# 128x64.net
KiCad netlist of a schematic drawn in Altium Designer
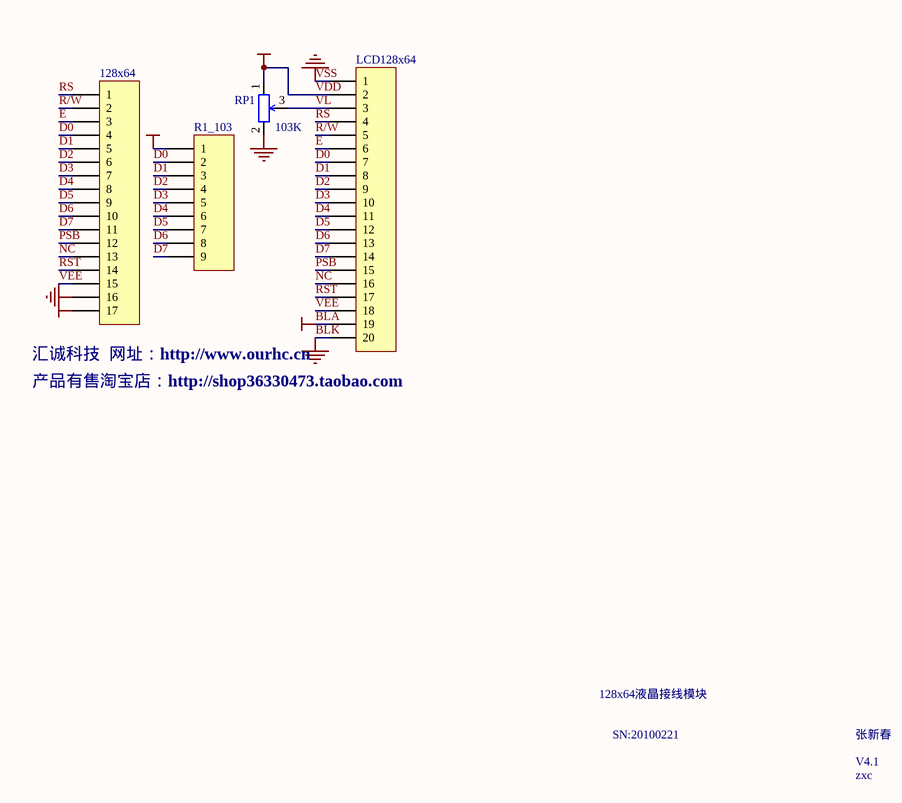
[diagram p0: 128x64液晶接线模块.SCHDOC]

(export (version "E")
  (design (tool "Eeschema 10.0.6"))
  (components
    (comp (ref "128x64")
      (value "Header 17")
      (footprint "HDR1X17")
      (description "Header, 17-Pin")
      (fields (field (name "PUBLISHER") "Altium Limited"))
      (libsource (lib "Miscellaneous Connectors") (part "Header 17"))
    )
    (comp (ref "LCD128x64")
      (value "Header 20")
      (footprint "HDR1X20")
      (description "Header, 20-Pin")
      (fields (field (name "PUBLISHER") "Altium Limited"))
      (libsource (lib "Miscellaneous Connectors") (part "Header 20"))
    )
    (comp (ref "R1_103")
      (value "Header 9")
      (footprint "HDR1X9")
      (description "Header, 9-Pin")
      (fields (field (name "PUBLISHER") "Altium Limited"))
      (libsource (lib "Miscellaneous Connectors") (part "Header 9"))
    )
    (comp (ref "RP1")
      (value "103K")
      (footprint "SIP3-D")
      (description "j精调电阻")
      (fields (field (name "Comment") "Res _JT") (field (name "PUBLISHER") "Altium Limited"))
      (libsource (lib "zxcourhc") (part "Res _JT"))
    )
  )
  (nets
    (net (code "1") (name "/D0") (class "Default")
      (node (ref "128x64") (pin "4") (pinfunction "4_4") (pintype "passive"))
      (node (ref "LCD128x64") (pin "7") (pinfunction "7_7") (pintype "passive"))
      (node (ref "R1_103") (pin "2") (pinfunction "2_2") (pintype "passive"))
    )
    (net (code "2") (name "/D1") (class "Default")
      (node (ref "128x64") (pin "5") (pinfunction "5_5") (pintype "passive"))
      (node (ref "LCD128x64") (pin "8") (pinfunction "8_8") (pintype "passive"))
      (node (ref "R1_103") (pin "3") (pinfunction "3_3") (pintype "passive"))
    )
    (net (code "3") (name "/D2") (class "Default")
      (node (ref "128x64") (pin "6") (pinfunction "6_6") (pintype "passive"))
      (node (ref "LCD128x64") (pin "9") (pinfunction "9_9") (pintype "passive"))
      (node (ref "R1_103") (pin "4") (pinfunction "4_4") (pintype "passive"))
    )
    (net (code "4") (name "/D3") (class "Default")
      (node (ref "128x64") (pin "7") (pinfunction "7_7") (pintype "passive"))
      (node (ref "LCD128x64") (pin "10") (pinfunction "10_10") (pintype "passive"))
      (node (ref "R1_103") (pin "5") (pinfunction "5_5") (pintype "passive"))
    )
    (net (code "5") (name "/D4") (class "Default")
      (node (ref "128x64") (pin "8") (pinfunction "8_8") (pintype "passive"))
      (node (ref "LCD128x64") (pin "11") (pinfunction "11_11") (pintype "passive"))
      (node (ref "R1_103") (pin "6") (pinfunction "6_6") (pintype "passive"))
    )
    (net (code "6") (name "/D5") (class "Default")
      (node (ref "128x64") (pin "9") (pinfunction "9_9") (pintype "passive"))
      (node (ref "LCD128x64") (pin "12") (pinfunction "12_12") (pintype "passive"))
      (node (ref "R1_103") (pin "7") (pinfunction "7_7") (pintype "passive"))
    )
    (net (code "7") (name "/D6") (class "Default")
      (node (ref "128x64") (pin "10") (pinfunction "10_10") (pintype "passive"))
      (node (ref "LCD128x64") (pin "13") (pinfunction "13_13") (pintype "passive"))
      (node (ref "R1_103") (pin "8") (pinfunction "8_8") (pintype "passive"))
    )
    (net (code "8") (name "/D7") (class "Default")
      (node (ref "128x64") (pin "11") (pinfunction "11_11") (pintype "passive"))
      (node (ref "LCD128x64") (pin "14") (pinfunction "14_14") (pintype "passive"))
      (node (ref "R1_103") (pin "9") (pinfunction "9_9") (pintype "passive"))
    )
    (net (code "9") (name "/E") (class "Default")
      (node (ref "128x64") (pin "3") (pinfunction "3_3") (pintype "passive"))
      (node (ref "LCD128x64") (pin "6") (pinfunction "6_6") (pintype "passive"))
    )
    (net (code "10") (name "/NC") (class "Default")
      (node (ref "128x64") (pin "13") (pinfunction "13_13") (pintype "passive"))
      (node (ref "LCD128x64") (pin "16") (pinfunction "16_16") (pintype "passive"))
    )
    (net (code "11") (name "/PSB") (class "Default")
      (node (ref "128x64") (pin "12") (pinfunction "12_12") (pintype "passive"))
      (node (ref "LCD128x64") (pin "15") (pinfunction "15_15") (pintype "passive"))
    )
    (net (code "12") (name "/RS") (class "Default")
      (node (ref "128x64") (pin "1") (pinfunction "1_1") (pintype "passive"))
      (node (ref "LCD128x64") (pin "4") (pinfunction "4_4") (pintype "passive"))
    )
    (net (code "13") (name "/RST") (class "Default")
      (node (ref "128x64") (pin "14") (pinfunction "14_14") (pintype "passive"))
      (node (ref "LCD128x64") (pin "17") (pinfunction "17_17") (pintype "passive"))
    )
    (net (code "14") (name "/R{slash}W") (class "Default")
      (node (ref "128x64") (pin "2") (pinfunction "2_2") (pintype "passive"))
      (node (ref "LCD128x64") (pin "5") (pinfunction "5_5") (pintype "passive"))
    )
    (net (code "15") (name "/VEE") (class "Default")
      (node (ref "128x64") (pin "15") (pinfunction "15_15") (pintype "passive"))
      (node (ref "LCD128x64") (pin "18") (pinfunction "18_18") (pintype "passive"))
    )
    (net (code "16") (name "/VL") (class "Default")
      (node (ref "LCD128x64") (pin "3") (pinfunction "3_3") (pintype "passive"))
      (node (ref "RP1") (pin "3") (pinfunction "3_3") (pintype "passive"))
    )
    (net (code "17") (name "GND") (class "Default")
      (node (ref "128x64") (pin "16") (pinfunction "16_16") (pintype "passive"))
      (node (ref "LCD128x64") (pin "1") (pinfunction "1_1") (pintype "passive"))
      (node (ref "LCD128x64") (pin "20") (pinfunction "20_20") (pintype "passive"))
      (node (ref "RP1") (pin "2") (pinfunction "2_2") (pintype "passive"))
    )
    (net (code "18") (name "VCC") (class "Default")
      (node (ref "128x64") (pin "17") (pinfunction "17_17") (pintype "passive"))
      (node (ref "LCD128x64") (pin "19") (pinfunction "19_19") (pintype "passive"))
      (node (ref "LCD128x64") (pin "2") (pinfunction "2_2") (pintype "passive"))
      (node (ref "R1_103") (pin "1") (pinfunction "1_1") (pintype "passive"))
      (node (ref "RP1") (pin "1") (pinfunction "1_1") (pintype "passive"))
    )
  )
)
